# 17_LPDDR4_LPDDR4x_1.net
KiCad netlist of a schematic drawn in Altium Designer
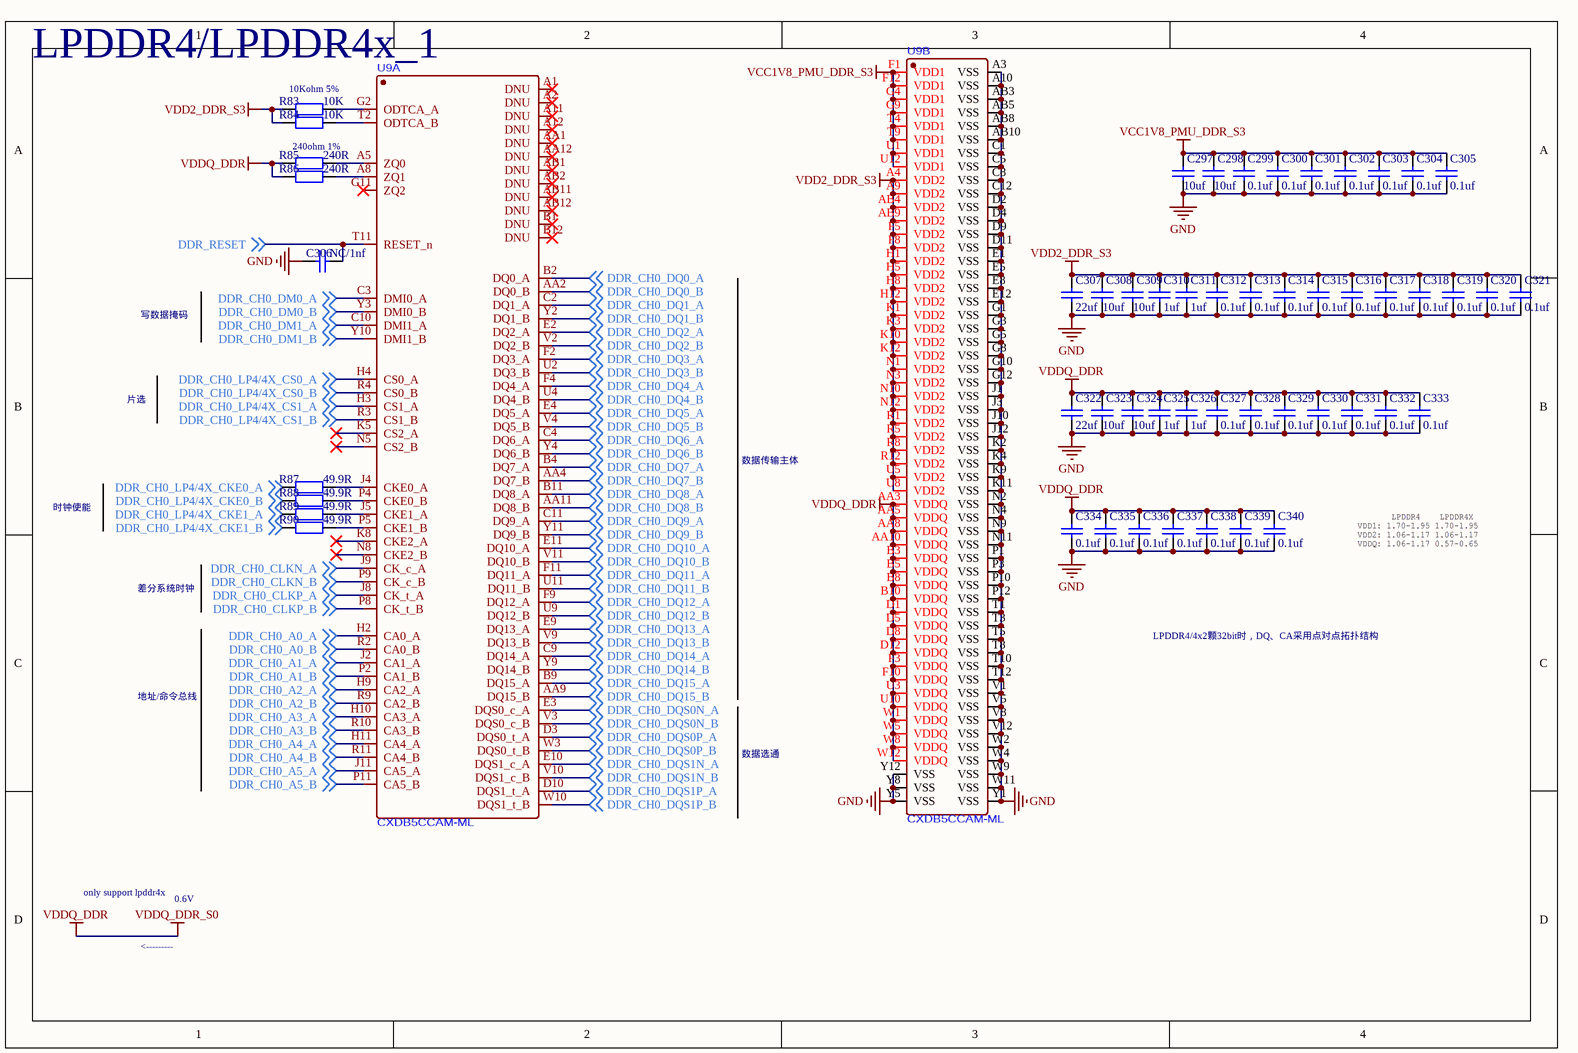
[diagram p0: 17.LPDDR4_LPDDR4x_1.SchDoc]

(export (version "E")
  (design (tool "Eeschema 10.0.6"))
  (components
    (comp (ref "C297")
      (value "10uf")
      (footprint "0.PCB1:C0402_L")
      (description "贴片电容/MLCC电容")
      (libsource (lib "RK3588") (part "C"))
    )
    (comp (ref "C298")
      (value "10uf")
      (footprint "0.PCB1:C0402_L")
      (description "贴片电容/MLCC电容")
      (libsource (lib "RK3588") (part "C"))
    )
    (comp (ref "C299")
      (value "0.1uf")
      (footprint "0.PCB1:C0201_L")
      (description "贴片电容/MLCC电容")
      (libsource (lib "RK3588") (part "C"))
    )
    (comp (ref "C300")
      (value "0.1uf")
      (footprint "0.PCB1:C0201_L")
      (description "贴片电容/MLCC电容")
      (libsource (lib "RK3588") (part "C"))
    )
    (comp (ref "C301")
      (value "0.1uf")
      (footprint "0.PCB1:C0201_L")
      (description "贴片电容/MLCC电容")
      (libsource (lib "RK3588") (part "C"))
    )
    (comp (ref "C302")
      (value "0.1uf")
      (footprint "0.PCB1:C0201_L")
      (description "贴片电容/MLCC电容")
      (libsource (lib "RK3588") (part "C"))
    )
    (comp (ref "C303")
      (value "0.1uf")
      (footprint "0.PCB1:C0201_L")
      (description "贴片电容/MLCC电容")
      (libsource (lib "RK3588") (part "C"))
    )
    (comp (ref "C304")
      (value "0.1uf")
      (footprint "0.PCB1:C0201_L")
      (description "贴片电容/MLCC电容")
      (libsource (lib "RK3588") (part "C"))
    )
    (comp (ref "C305")
      (value "0.1uf")
      (footprint "0.PCB1:C0201_L")
      (description "贴片电容/MLCC电容")
      (libsource (lib "RK3588") (part "C"))
    )
    (comp (ref "C306")
      (value "NC/1nf")
      (footprint "0.PCB1:C0201_L")
      (description "贴片电容/MLCC电容")
      (libsource (lib "RK3588") (part "C"))
    )
    (comp (ref "C307")
      (value "22uf")
      (footprint "0.PCB1:C0603_L")
      (description "贴片电容/MLCC电容")
      (libsource (lib "RK3588") (part "C"))
    )
    (comp (ref "C308")
      (value "10uf")
      (footprint "0.PCB1:C0402_L")
      (description "贴片电容/MLCC电容")
      (libsource (lib "RK3588") (part "C"))
    )
    (comp (ref "C309")
      (value "10uf")
      (footprint "0.PCB1:C0402_L")
      (description "贴片电容/MLCC电容")
      (libsource (lib "RK3588") (part "C"))
    )
    (comp (ref "C310")
      (value "1uf")
      (footprint "0.PCB1:C0201_L")
      (description "贴片电容/MLCC电容")
      (libsource (lib "RK3588") (part "C"))
    )
    (comp (ref "C311")
      (value "1uf")
      (footprint "0.PCB1:C0201_L")
      (description "贴片电容/MLCC电容")
      (libsource (lib "RK3588") (part "C"))
    )
    (comp (ref "C312")
      (value "0.1uf")
      (footprint "0.PCB1:C0201_L")
      (description "贴片电容/MLCC电容")
      (libsource (lib "RK3588") (part "C"))
    )
    (comp (ref "C313")
      (value "0.1uf")
      (footprint "0.PCB1:C0201_L")
      (description "贴片电容/MLCC电容")
      (libsource (lib "RK3588") (part "C"))
    )
    (comp (ref "C314")
      (value "0.1uf")
      (footprint "0.PCB1:C0201_L")
      (description "贴片电容/MLCC电容")
      (libsource (lib "RK3588") (part "C"))
    )
    (comp (ref "C315")
      (value "0.1uf")
      (footprint "0.PCB1:C0201_L")
      (description "贴片电容/MLCC电容")
      (libsource (lib "RK3588") (part "C"))
    )
    (comp (ref "C316")
      (value "0.1uf")
      (footprint "0.PCB1:C0201_L")
      (description "贴片电容/MLCC电容")
      (libsource (lib "RK3588") (part "C"))
    )
    (comp (ref "C317")
      (value "0.1uf")
      (footprint "0.PCB1:C0201_L")
      (description "贴片电容/MLCC电容")
      (libsource (lib "RK3588") (part "C"))
    )
    (comp (ref "C318")
      (value "0.1uf")
      (footprint "0.PCB1:C0201_L")
      (description "贴片电容/MLCC电容")
      (libsource (lib "RK3588") (part "C"))
    )
    (comp (ref "C319")
      (value "0.1uf")
      (footprint "0.PCB1:C0201_L")
      (description "贴片电容/MLCC电容")
      (libsource (lib "RK3588") (part "C"))
    )
    (comp (ref "C320")
      (value "0.1uf")
      (footprint "0.PCB1:C0201_L")
      (description "贴片电容/MLCC电容")
      (libsource (lib "RK3588") (part "C"))
    )
    (comp (ref "C321")
      (value "0.1uf")
      (footprint "0.PCB1:C0201_L")
      (description "贴片电容/MLCC电容")
      (libsource (lib "RK3588") (part "C"))
    )
    (comp (ref "C322")
      (value "22uf")
      (footprint "0.PCB1:C0603_L")
      (description "贴片电容/MLCC电容")
      (libsource (lib "RK3588") (part "C"))
    )
    (comp (ref "C323")
      (value "10uf")
      (footprint "0.PCB1:C0402_L")
      (description "贴片电容/MLCC电容")
      (libsource (lib "RK3588") (part "C"))
    )
    (comp (ref "C324")
      (value "10uf")
      (footprint "0.PCB1:C0402_L")
      (description "贴片电容/MLCC电容")
      (libsource (lib "RK3588") (part "C"))
    )
    (comp (ref "C325")
      (value "1uf")
      (footprint "0.PCB1:C0201_L")
      (description "贴片电容/MLCC电容")
      (libsource (lib "RK3588") (part "C"))
    )
    (comp (ref "C326")
      (value "1uf")
      (footprint "0.PCB1:C0201_L")
      (description "贴片电容/MLCC电容")
      (libsource (lib "RK3588") (part "C"))
    )
    (comp (ref "C327")
      (value "0.1uf")
      (footprint "0.PCB1:C0201_L")
      (description "贴片电容/MLCC电容")
      (libsource (lib "RK3588") (part "C"))
    )
    (comp (ref "C328")
      (value "0.1uf")
      (footprint "0.PCB1:C0201_L")
      (description "贴片电容/MLCC电容")
      (libsource (lib "RK3588") (part "C"))
    )
    (comp (ref "C329")
      (value "0.1uf")
      (footprint "0.PCB1:C0201_L")
      (description "贴片电容/MLCC电容")
      (libsource (lib "RK3588") (part "C"))
    )
    (comp (ref "C330")
      (value "0.1uf")
      (footprint "0.PCB1:C0201_L")
      (description "贴片电容/MLCC电容")
      (libsource (lib "RK3588") (part "C"))
    )
    (comp (ref "C331")
      (value "0.1uf")
      (footprint "0.PCB1:C0201_L")
      (description "贴片电容/MLCC电容")
      (libsource (lib "RK3588") (part "C"))
    )
    (comp (ref "C332")
      (value "0.1uf")
      (footprint "0.PCB1:C0201_L")
      (description "贴片电容/MLCC电容")
      (libsource (lib "RK3588") (part "C"))
    )
    (comp (ref "C333")
      (value "0.1uf")
      (footprint "0.PCB1:C0201_L")
      (description "贴片电容/MLCC电容")
      (libsource (lib "RK3588") (part "C"))
    )
    (comp (ref "C334")
      (value "0.1uf")
      (footprint "0.PCB1:C0201_L")
      (description "贴片电容/MLCC电容")
      (libsource (lib "RK3588") (part "C"))
    )
    (comp (ref "C335")
      (value "0.1uf")
      (footprint "0.PCB1:C0201_L")
      (description "贴片电容/MLCC电容")
      (libsource (lib "RK3588") (part "C"))
    )
    (comp (ref "C336")
      (value "0.1uf")
      (footprint "0.PCB1:C0201_L")
      (description "贴片电容/MLCC电容")
      (libsource (lib "RK3588") (part "C"))
    )
    (comp (ref "C337")
      (value "0.1uf")
      (footprint "0.PCB1:C0201_L")
      (description "贴片电容/MLCC电容")
      (libsource (lib "RK3588") (part "C"))
    )
    (comp (ref "C338")
      (value "0.1uf")
      (footprint "0.PCB1:C0201_L")
      (description "贴片电容/MLCC电容")
      (libsource (lib "RK3588") (part "C"))
    )
    (comp (ref "C339")
      (value "0.1uf")
      (footprint "0.PCB1:C0201_L")
      (description "贴片电容/MLCC电容")
      (libsource (lib "RK3588") (part "C"))
    )
    (comp (ref "C340")
      (value "0.1uf")
      (footprint "0.PCB1:C0201_L")
      (description "贴片电容/MLCC电容")
      (libsource (lib "RK3588") (part "C"))
    )
    (comp (ref "R83")
      (value "10K")
      (footprint "0.PCB1:R0201_L")
      (description "贴片电阻")
      (libsource (lib "RK3588") (part "R"))
    )
    (comp (ref "R84")
      (value "10K")
      (footprint "0.PCB1:R0201_L")
      (description "贴片电阻")
      (libsource (lib "RK3588") (part "R"))
    )
    (comp (ref "R85")
      (value "240R")
      (footprint "0.PCB1:R0201_L")
      (description "贴片电阻")
      (libsource (lib "RK3588") (part "R"))
    )
    (comp (ref "R86")
      (value "240R")
      (footprint "0.PCB1:R0201_L")
      (description "贴片电阻")
      (libsource (lib "RK3588") (part "R"))
    )
    (comp (ref "R87")
      (value "49.9R")
      (footprint "0.PCB1:R0201_L")
      (description "贴片电阻")
      (libsource (lib "RK3588") (part "R"))
    )
    (comp (ref "R88")
      (value "49.9R")
      (footprint "0.PCB1:R0201_L")
      (description "贴片电阻")
      (libsource (lib "RK3588") (part "R"))
    )
    (comp (ref "R89")
      (value "49.9R")
      (footprint "0.PCB1:R0201_L")
      (description "贴片电阻")
      (libsource (lib "RK3588") (part "R"))
    )
    (comp (ref "R90")
      (value "49.9R")
      (footprint "0.PCB1:R0201_L")
      (description "贴片电阻")
      (libsource (lib "RK3588") (part "R"))
    )
    (comp (ref "U9")
      (value "CXDB5CCAM-ML")
      (footprint "0.PCB1:FBGA-200_L15.0-W10.0-BL_K4F6E3S4HM")
      (libsource (lib "RK3588") (part "CXDB5CCAM-ML"))
    )
  )
  (nets
    (net (code "1") (name "DDR_CH0_A0_A") (class "Default")
      (node (ref "U9") (pin "H2") (pinfunction "CA0_A_H2") (pintype "passive"))
    )
    (net (code "2") (name "DDR_CH0_A0_B") (class "Default")
      (node (ref "U9") (pin "R2") (pinfunction "CA0_B_R2") (pintype "passive"))
    )
    (net (code "3") (name "DDR_CH0_A1_A") (class "Default")
      (node (ref "U9") (pin "J2") (pinfunction "CA1_A_J2") (pintype "passive"))
    )
    (net (code "4") (name "DDR_CH0_A1_B") (class "Default")
      (node (ref "U9") (pin "P2") (pinfunction "CA1_B_P2") (pintype "passive"))
    )
    (net (code "5") (name "DDR_CH0_A2_A") (class "Default")
      (node (ref "U9") (pin "H9") (pinfunction "CA2_A_H9") (pintype "passive"))
    )
    (net (code "6") (name "DDR_CH0_A2_B") (class "Default")
      (node (ref "U9") (pin "R9") (pinfunction "CA2_B_R9") (pintype "passive"))
    )
    (net (code "7") (name "DDR_CH0_A3_A") (class "Default")
      (node (ref "U9") (pin "H10") (pinfunction "CA3_A_H10") (pintype "passive"))
    )
    (net (code "8") (name "DDR_CH0_A3_B") (class "Default")
      (node (ref "U9") (pin "R10") (pinfunction "CA3_B_R10") (pintype "passive"))
    )
    (net (code "9") (name "DDR_CH0_A4_A") (class "Default")
      (node (ref "U9") (pin "H11") (pinfunction "CA4_A_H11") (pintype "passive"))
    )
    (net (code "10") (name "DDR_CH0_A4_B") (class "Default")
      (node (ref "U9") (pin "R11") (pinfunction "CA4_B_R11") (pintype "passive"))
    )
    (net (code "11") (name "DDR_CH0_A5_A") (class "Default")
      (node (ref "U9") (pin "J11") (pinfunction "CA5_A_J11") (pintype "passive"))
    )
    (net (code "12") (name "DDR_CH0_A5_B") (class "Default")
      (node (ref "U9") (pin "P11") (pinfunction "CA5_B_P11") (pintype "passive"))
    )
    (net (code "13") (name "DDR_CH0_CLKN_A") (class "Default")
      (node (ref "U9") (pin "J9") (pinfunction "CK_c_A_J9") (pintype "passive"))
    )
    (net (code "14") (name "DDR_CH0_CLKN_B") (class "Default")
      (node (ref "U9") (pin "P9") (pinfunction "CK_c_B_P9") (pintype "passive"))
    )
    (net (code "15") (name "DDR_CH0_CLKP_A") (class "Default")
      (node (ref "U9") (pin "J8") (pinfunction "CK_t_A_J8") (pintype "passive"))
    )
    (net (code "16") (name "DDR_CH0_CLKP_B") (class "Default")
      (node (ref "U9") (pin "P8") (pinfunction "CK_t_B_P8") (pintype "passive"))
    )
    (net (code "17") (name "DDR_CH0_DM0_A") (class "Default")
      (node (ref "U9") (pin "C3") (pinfunction "DMI0_A_C3") (pintype "passive"))
    )
    (net (code "18") (name "DDR_CH0_DM0_B") (class "Default")
      (node (ref "U9") (pin "Y3") (pinfunction "DMI0_B_Y3") (pintype "passive"))
    )
    (net (code "19") (name "DDR_CH0_DM1_A") (class "Default")
      (node (ref "U9") (pin "C10") (pinfunction "DMI1_A_C10") (pintype "passive"))
    )
    (net (code "20") (name "DDR_CH0_DM1_B") (class "Default")
      (node (ref "U9") (pin "Y10") (pinfunction "DMI1_B_Y10") (pintype "passive"))
    )
    (net (code "21") (name "DDR_CH0_DQ0_A") (class "Default")
      (node (ref "U9") (pin "B2") (pinfunction "DQ0_A_B2") (pintype "passive"))
    )
    (net (code "22") (name "DDR_CH0_DQ0_B") (class "Default")
      (node (ref "U9") (pin "AA2") (pinfunction "DQ0_B_AA2") (pintype "passive"))
    )
    (net (code "23") (name "DDR_CH0_DQ1_A") (class "Default")
      (node (ref "U9") (pin "C2") (pinfunction "DQ1_A_C2") (pintype "passive"))
    )
    (net (code "24") (name "DDR_CH0_DQ1_B") (class "Default")
      (node (ref "U9") (pin "Y2") (pinfunction "DQ1_B_Y2") (pintype "passive"))
    )
    (net (code "25") (name "DDR_CH0_DQ2_A") (class "Default")
      (node (ref "U9") (pin "E2") (pinfunction "DQ2_A_E2") (pintype "passive"))
    )
    (net (code "26") (name "DDR_CH0_DQ2_B") (class "Default")
      (node (ref "U9") (pin "V2") (pinfunction "DQ2_B_V2") (pintype "passive"))
    )
    (net (code "27") (name "DDR_CH0_DQ3_A") (class "Default")
      (node (ref "U9") (pin "F2") (pinfunction "DQ3_A_F2") (pintype "passive"))
    )
    (net (code "28") (name "DDR_CH0_DQ3_B") (class "Default")
      (node (ref "U9") (pin "U2") (pinfunction "DQ3_B_U2") (pintype "passive"))
    )
    (net (code "29") (name "DDR_CH0_DQ4_A") (class "Default")
      (node (ref "U9") (pin "F4") (pinfunction "DQ4_A_F4") (pintype "passive"))
    )
    (net (code "30") (name "DDR_CH0_DQ4_B") (class "Default")
      (node (ref "U9") (pin "U4") (pinfunction "DQ4_B_U4") (pintype "passive"))
    )
    (net (code "31") (name "DDR_CH0_DQ5_A") (class "Default")
      (node (ref "U9") (pin "E4") (pinfunction "DQ5_A_E4") (pintype "passive"))
    )
    (net (code "32") (name "DDR_CH0_DQ5_B") (class "Default")
      (node (ref "U9") (pin "V4") (pinfunction "DQ5_B_V4") (pintype "passive"))
    )
    (net (code "33") (name "DDR_CH0_DQ6_A") (class "Default")
      (node (ref "U9") (pin "C4") (pinfunction "DQ6_A_C4") (pintype "passive"))
    )
    (net (code "34") (name "DDR_CH0_DQ6_B") (class "Default")
      (node (ref "U9") (pin "Y4") (pinfunction "DQ6_B_Y4") (pintype "passive"))
    )
    (net (code "35") (name "DDR_CH0_DQ7_A") (class "Default")
      (node (ref "U9") (pin "B4") (pinfunction "DQ7_A_B4") (pintype "passive"))
    )
    (net (code "36") (name "DDR_CH0_DQ7_B") (class "Default")
      (node (ref "U9") (pin "AA4") (pinfunction "DQ7_B_AA4") (pintype "passive"))
    )
    (net (code "37") (name "DDR_CH0_DQ8_A") (class "Default")
      (node (ref "U9") (pin "B11") (pinfunction "DQ8_A_B11") (pintype "passive"))
    )
    (net (code "38") (name "DDR_CH0_DQ8_B") (class "Default")
      (node (ref "U9") (pin "AA11") (pinfunction "DQ8_B_AA11") (pintype "passive"))
    )
    (net (code "39") (name "DDR_CH0_DQ9_A") (class "Default")
      (node (ref "U9") (pin "C11") (pinfunction "DQ9_A_C11") (pintype "passive"))
    )
    (net (code "40") (name "DDR_CH0_DQ9_B") (class "Default")
      (node (ref "U9") (pin "Y11") (pinfunction "DQ9_B_Y11") (pintype "passive"))
    )
    (net (code "41") (name "DDR_CH0_DQ10_A") (class "Default")
      (node (ref "U9") (pin "E11") (pinfunction "DQ10_A_E11") (pintype "passive"))
    )
    (net (code "42") (name "DDR_CH0_DQ10_B") (class "Default")
      (node (ref "U9") (pin "V11") (pinfunction "DQ10_B_V11") (pintype "passive"))
    )
    (net (code "43") (name "DDR_CH0_DQ11_A") (class "Default")
      (node (ref "U9") (pin "F11") (pinfunction "DQ11_A_F11") (pintype "passive"))
    )
    (net (code "44") (name "DDR_CH0_DQ11_B") (class "Default")
      (node (ref "U9") (pin "U11") (pinfunction "DQ11_B_U11") (pintype "passive"))
    )
    (net (code "45") (name "DDR_CH0_DQ12_A") (class "Default")
      (node (ref "U9") (pin "F9") (pinfunction "DQ12_A_F9") (pintype "passive"))
    )
    (net (code "46") (name "DDR_CH0_DQ12_B") (class "Default")
      (node (ref "U9") (pin "U9") (pinfunction "DQ12_B_U9") (pintype "passive"))
    )
    (net (code "47") (name "DDR_CH0_DQ13_A") (class "Default")
      (node (ref "U9") (pin "E9") (pinfunction "DQ13_A_E9") (pintype "passive"))
    )
    (net (code "48") (name "DDR_CH0_DQ13_B") (class "Default")
      (node (ref "U9") (pin "V9") (pinfunction "DQ13_B_V9") (pintype "passive"))
    )
    (net (code "49") (name "DDR_CH0_DQ14_A") (class "Default")
      (node (ref "U9") (pin "C9") (pinfunction "DQ14_A_C9") (pintype "passive"))
    )
    (net (code "50") (name "DDR_CH0_DQ14_B") (class "Default")
      (node (ref "U9") (pin "Y9") (pinfunction "DQ14_B_Y9") (pintype "passive"))
    )
    (net (code "51") (name "DDR_CH0_DQ15_A") (class "Default")
      (node (ref "U9") (pin "B9") (pinfunction "DQ15_A_B9") (pintype "passive"))
    )
    (net (code "52") (name "DDR_CH0_DQ15_B") (class "Default")
      (node (ref "U9") (pin "AA9") (pinfunction "DQ15_B_AA9") (pintype "passive"))
    )
    (net (code "53") (name "DDR_CH0_DQS0N_A") (class "Default")
      (node (ref "U9") (pin "E3") (pinfunction "DQS0_c_A_E3") (pintype "passive"))
    )
    (net (code "54") (name "DDR_CH0_DQS0N_B") (class "Default")
      (node (ref "U9") (pin "V3") (pinfunction "DQS0_c_B_V3") (pintype "passive"))
    )
    (net (code "55") (name "DDR_CH0_DQS0P_A") (class "Default")
      (node (ref "U9") (pin "D3") (pinfunction "DQS0_t_A_D3") (pintype "passive"))
    )
    (net (code "56") (name "DDR_CH0_DQS0P_B") (class "Default")
      (node (ref "U9") (pin "W3") (pinfunction "DQS0_t_B_W3") (pintype "passive"))
    )
    (net (code "57") (name "DDR_CH0_DQS1N_A") (class "Default")
      (node (ref "U9") (pin "E10") (pinfunction "DQS1_c_A_E10") (pintype "passive"))
    )
    (net (code "58") (name "DDR_CH0_DQS1N_B") (class "Default")
      (node (ref "U9") (pin "V10") (pinfunction "DQS1_c_B_V10") (pintype "passive"))
    )
    (net (code "59") (name "DDR_CH0_DQS1P_A") (class "Default")
      (node (ref "U9") (pin "D10") (pinfunction "DQS1_t_A_D10") (pintype "passive"))
    )
    (net (code "60") (name "DDR_CH0_DQS1P_B") (class "Default")
      (node (ref "U9") (pin "W10") (pinfunction "DQS1_t_B_W10") (pintype "passive"))
    )
    (net (code "61") (name "DDR_CH0_LP4{slash}4X_CKE0_A") (class "Default")
      (node (ref "R87") (pin "1") (pinfunction "1_1") (pintype "passive"))
    )
    (net (code "62") (name "DDR_CH0_LP4{slash}4X_CKE0_B") (class "Default")
      (node (ref "R88") (pin "1") (pinfunction "1_1") (pintype "passive"))
    )
    (net (code "63") (name "DDR_CH0_LP4{slash}4X_CKE1_A") (class "Default")
      (node (ref "R89") (pin "1") (pinfunction "1_1") (pintype "passive"))
    )
    (net (code "64") (name "DDR_CH0_LP4{slash}4X_CKE1_B") (class "Default")
      (node (ref "R90") (pin "1") (pinfunction "1_1") (pintype "passive"))
    )
    (net (code "65") (name "DDR_CH0_LP4{slash}4X_CS0_A") (class "Default")
      (node (ref "U9") (pin "H4") (pinfunction "CS0_A_H4") (pintype "passive"))
    )
    (net (code "66") (name "DDR_CH0_LP4{slash}4X_CS0_B") (class "Default")
      (node (ref "U9") (pin "R4") (pinfunction "CS0_B_R4") (pintype "passive"))
    )
    (net (code "67") (name "DDR_CH0_LP4{slash}4X_CS1_A") (class "Default")
      (node (ref "U9") (pin "H3") (pinfunction "CS1_A_H3") (pintype "passive"))
    )
    (net (code "68") (name "DDR_CH0_LP4{slash}4X_CS1_B") (class "Default")
      (node (ref "U9") (pin "R3") (pinfunction "CS1_B_R3") (pintype "passive"))
    )
    (net (code "69") (name "DDR_RESET") (class "Default")
      (node (ref "C306") (pin "2") (pinfunction "2_2") (pintype "passive"))
      (node (ref "U9") (pin "T11") (pinfunction "RESET_n_T11") (pintype "passive"))
    )
    (net (code "70") (name "GND") (class "Default")
      (node (ref "C297") (pin "1") (pinfunction "1_1") (pintype "passive"))
      (node (ref "C298") (pin "1") (pinfunction "1_1") (pintype "passive"))
      (node (ref "C299") (pin "1") (pinfunction "1_1") (pintype "passive"))
      (node (ref "C300") (pin "1") (pinfunction "1_1") (pintype "passive"))
      (node (ref "C301") (pin "1") (pinfunction "1_1") (pintype "passive"))
      (node (ref "C302") (pin "1") (pinfunction "1_1") (pintype "passive"))
      (node (ref "C303") (pin "1") (pinfunction "1_1") (pintype "passive"))
      (node (ref "C304") (pin "1") (pinfunction "1_1") (pintype "passive"))
      (node (ref "C305") (pin "1") (pinfunction "1_1") (pintype "passive"))
      (node (ref "C306") (pin "1") (pinfunction "1_1") (pintype "passive"))
      (node (ref "C307") (pin "1") (pinfunction "1_1") (pintype "passive"))
      (node (ref "C308") (pin "1") (pinfunction "1_1") (pintype "passive"))
      (node (ref "C309") (pin "1") (pinfunction "1_1") (pintype "passive"))
      (node (ref "C310") (pin "1") (pinfunction "1_1") (pintype "passive"))
      (node (ref "C311") (pin "1") (pinfunction "1_1") (pintype "passive"))
      (node (ref "C312") (pin "1") (pinfunction "1_1") (pintype "passive"))
      (node (ref "C313") (pin "1") (pinfunction "1_1") (pintype "passive"))
      (node (ref "C314") (pin "1") (pinfunction "1_1") (pintype "passive"))
      (node (ref "C315") (pin "1") (pinfunction "1_1") (pintype "passive"))
      (node (ref "C316") (pin "1") (pinfunction "1_1") (pintype "passive"))
      (node (ref "C317") (pin "1") (pinfunction "1_1") (pintype "passive"))
      (node (ref "C318") (pin "1") (pinfunction "1_1") (pintype "passive"))
      (node (ref "C319") (pin "1") (pinfunction "1_1") (pintype "passive"))
      (node (ref "C320") (pin "1") (pinfunction "1_1") (pintype "passive"))
      (node (ref "C321") (pin "1") (pinfunction "1_1") (pintype "passive"))
      (node (ref "C322") (pin "1") (pinfunction "1_1") (pintype "passive"))
      (node (ref "C323") (pin "1") (pinfunction "1_1") (pintype "passive"))
      (node (ref "C324") (pin "1") (pinfunction "1_1") (pintype "passive"))
      (node (ref "C325") (pin "1") (pinfunction "1_1") (pintype "passive"))
      (node (ref "C326") (pin "1") (pinfunction "1_1") (pintype "passive"))
      (node (ref "C327") (pin "1") (pinfunction "1_1") (pintype "passive"))
      (node (ref "C328") (pin "1") (pinfunction "1_1") (pintype "passive"))
      (node (ref "C329") (pin "1") (pinfunction "1_1") (pintype "passive"))
      (node (ref "C330") (pin "1") (pinfunction "1_1") (pintype "passive"))
      (node (ref "C331") (pin "1") (pinfunction "1_1") (pintype "passive"))
      (node (ref "C332") (pin "1") (pinfunction "1_1") (pintype "passive"))
      (node (ref "C333") (pin "1") (pinfunction "1_1") (pintype "passive"))
      (node (ref "C334") (pin "1") (pinfunction "1_1") (pintype "passive"))
      (node (ref "C335") (pin "1") (pinfunction "1_1") (pintype "passive"))
      (node (ref "C336") (pin "1") (pinfunction "1_1") (pintype "passive"))
      (node (ref "C337") (pin "1") (pinfunction "1_1") (pintype "passive"))
      (node (ref "C338") (pin "1") (pinfunction "1_1") (pintype "passive"))
      (node (ref "C339") (pin "1") (pinfunction "1_1") (pintype "passive"))
      (node (ref "C340") (pin "1") (pinfunction "1_1") (pintype "passive"))
      (node (ref "U9") (pin "A10") (pinfunction "VSS_A10") (pintype "passive"))
      (node (ref "U9") (pin "A3") (pinfunction "VSS_A3") (pintype "passive"))
      (node (ref "U9") (pin "AB10") (pinfunction "VSS_AB10") (pintype "passive"))
      (node (ref "U9") (pin "AB3") (pinfunction "VSS_AB3") (pintype "passive"))
      (node (ref "U9") (pin "AB5") (pinfunction "VSS_AB5") (pintype "passive"))
      (node (ref "U9") (pin "AB8") (pinfunction "VSS_AB8") (pintype "passive"))
      (node (ref "U9") (pin "C1") (pinfunction "VSS_C1") (pintype "passive"))
      (node (ref "U9") (pin "C12") (pinfunction "VSS_C12") (pintype "passive"))
      (node (ref "U9") (pin "C5") (pinfunction "VSS_C5") (pintype "passive"))
      (node (ref "U9") (pin "C8") (pinfunction "VSS_C8") (pintype "passive"))
      (node (ref "U9") (pin "D11") (pinfunction "VSS_D11") (pintype "passive"))
      (node (ref "U9") (pin "D2") (pinfunction "VSS_D2") (pintype "passive"))
      (node (ref "U9") (pin "D4") (pinfunction "VSS_D4") (pintype "passive"))
      (node (ref "U9") (pin "D9") (pinfunction "VSS_D9") (pintype "passive"))
      (node (ref "U9") (pin "E1") (pinfunction "VSS_E1") (pintype "passive"))
      (node (ref "U9") (pin "E12") (pinfunction "VSS_E12") (pintype "passive"))
      (node (ref "U9") (pin "E5") (pinfunction "VSS_E5") (pintype "passive"))
      (node (ref "U9") (pin "E8") (pinfunction "VSS_E8") (pintype "passive"))
      (node (ref "U9") (pin "G1") (pinfunction "VSS_G1") (pintype "passive"))
      (node (ref "U9") (pin "G10") (pinfunction "VSS_G10") (pintype "passive"))
      (node (ref "U9") (pin "G12") (pinfunction "VSS_G12") (pintype "passive"))
      (node (ref "U9") (pin "G3") (pinfunction "VSS_G3") (pintype "passive"))
      (node (ref "U9") (pin "G5") (pinfunction "VSS_G5") (pintype "passive"))
      (node (ref "U9") (pin "G8") (pinfunction "VSS_G8") (pintype "passive"))
      (node (ref "U9") (pin "J1") (pinfunction "VSS_J1") (pintype "passive"))
      (node (ref "U9") (pin "J10") (pinfunction "VSS_J10") (pintype "passive"))
      (node (ref "U9") (pin "J12") (pinfunction "VSS_J12") (pintype "passive"))
      (node (ref "U9") (pin "J3") (pinfunction "VSS_J3") (pintype "passive"))
      (node (ref "U9") (pin "K11") (pinfunction "VSS_K11") (pintype "passive"))
      (node (ref "U9") (pin "K2") (pinfunction "VSS_K2") (pintype "passive"))
      (node (ref "U9") (pin "K4") (pinfunction "VSS_K4") (pintype "passive"))
      (node (ref "U9") (pin "K9") (pinfunction "VSS_K9") (pintype "passive"))
      (node (ref "U9") (pin "N11") (pinfunction "VSS_N11") (pintype "passive"))
      (node (ref "U9") (pin "N2") (pinfunction "VSS_N2") (pintype "passive"))
      (node (ref "U9") (pin "N4") (pinfunction "VSS_N4") (pintype "passive"))
      (node (ref "U9") (pin "N9") (pinfunction "VSS_N9") (pintype "passive"))
      (node (ref "U9") (pin "P1") (pinfunction "VSS_P1") (pintype "passive"))
      (node (ref "U9") (pin "P10") (pinfunction "VSS_P10") (pintype "passive"))
      (node (ref "U9") (pin "P12") (pinfunction "VSS_P12") (pintype "passive"))
      (node (ref "U9") (pin "P3") (pinfunction "VSS_P3") (pintype "passive"))
      (node (ref "U9") (pin "T1") (pinfunction "VSS_T1") (pintype "passive"))
      (node (ref "U9") (pin "T10") (pinfunction "VSS_T10") (pintype "passive"))
      (node (ref "U9") (pin "T12") (pinfunction "VSS_T12") (pintype "passive"))
      (node (ref "U9") (pin "T3") (pinfunction "VSS_T3") (pintype "passive"))
      (node (ref "U9") (pin "T5") (pinfunction "VSS_T5") (pintype "passive"))
      (node (ref "U9") (pin "T8") (pinfunction "VSS_T8") (pintype "passive"))
      (node (ref "U9") (pin "V1") (pinfunction "VSS_V1") (pintype "passive"))
      (node (ref "U9") (pin "V12") (pinfunction "VSS_V12") (pintype "passive"))
      (node (ref "U9") (pin "V5") (pinfunction "VSS_V5") (pintype "passive"))
      (node (ref "U9") (pin "V8") (pinfunction "VSS_V8") (pintype "passive"))
      (node (ref "U9") (pin "W11") (pinfunction "VSS_W11") (pintype "passive"))
      (node (ref "U9") (pin "W2") (pinfunction "VSS_W2") (pintype "passive"))
      (node (ref "U9") (pin "W4") (pinfunction "VSS_W4") (pintype "passive"))
      (node (ref "U9") (pin "W9") (pinfunction "VSS_W9") (pintype "passive"))
      (node (ref "U9") (pin "Y1") (pinfunction "VSS_Y1") (pintype "passive"))
      (node (ref "U9") (pin "Y12") (pinfunction "VSS_Y12") (pintype "passive"))
      (node (ref "U9") (pin "Y5") (pinfunction "VSS_Y5") (pintype "passive"))
      (node (ref "U9") (pin "Y8") (pinfunction "VSS_Y8") (pintype "passive"))
    )
    (net (code "71") (name "Net-(U9A-CKE0_A)") (class "Default")
      (node (ref "R87") (pin "2") (pinfunction "2_2") (pintype "passive"))
      (node (ref "U9") (pin "J4") (pinfunction "CKE0_A_J4") (pintype "passive"))
    )
    (net (code "72") (name "Net-(U9A-CKE0_B)") (class "Default")
      (node (ref "R88") (pin "2") (pinfunction "2_2") (pintype "passive"))
      (node (ref "U9") (pin "P4") (pinfunction "CKE0_B_P4") (pintype "passive"))
    )
    (net (code "73") (name "Net-(U9A-CKE1_A)") (class "Default")
      (node (ref "R89") (pin "2") (pinfunction "2_2") (pintype "passive"))
      (node (ref "U9") (pin "J5") (pinfunction "CKE1_A_J5") (pintype "passive"))
    )
    (net (code "74") (name "Net-(U9A-CKE1_B)") (class "Default")
      (node (ref "R90") (pin "2") (pinfunction "2_2") (pintype "passive"))
      (node (ref "U9") (pin "P5") (pinfunction "CKE1_B_P5") (pintype "passive"))
    )
    (net (code "75") (name "Net-(U9A-ODTCA_A)") (class "Default")
      (node (ref "R83") (pin "2") (pinfunction "2_2") (pintype "passive"))
      (node (ref "U9") (pin "G2") (pinfunction "ODTCA_A_G2") (pintype "passive"))
    )
    (net (code "76") (name "Net-(U9A-ODTCA_B)") (class "Default")
      (node (ref "R84") (pin "2") (pinfunction "2_2") (pintype "passive"))
      (node (ref "U9") (pin "T2") (pinfunction "ODTCA_B_T2") (pintype "passive"))
    )
    (net (code "77") (name "Net-(U9A-ZQ0)") (class "Default")
      (node (ref "R85") (pin "2") (pinfunction "2_2") (pintype "passive"))
      (node (ref "U9") (pin "A5") (pinfunction "ZQ0_A5") (pintype "passive"))
    )
    (net (code "78") (name "Net-(U9A-ZQ1)") (class "Default")
      (node (ref "R86") (pin "2") (pinfunction "2_2") (pintype "passive"))
      (node (ref "U9") (pin "A8") (pinfunction "ZQ1_A8") (pintype "passive"))
    )
    (net (code "79") (name "VCC1V8_PMU_DDR_S3") (class "Default")
      (node (ref "C297") (pin "2") (pinfunction "2_2") (pintype "passive"))
      (node (ref "C298") (pin "2") (pinfunction "2_2") (pintype "passive"))
      (node (ref "C299") (pin "2") (pinfunction "2_2") (pintype "passive"))
      (node (ref "C300") (pin "2") (pinfunction "2_2") (pintype "passive"))
      (node (ref "C301") (pin "2") (pinfunction "2_2") (pintype "passive"))
      (node (ref "C302") (pin "2") (pinfunction "2_2") (pintype "passive"))
      (node (ref "C303") (pin "2") (pinfunction "2_2") (pintype "passive"))
      (node (ref "C304") (pin "2") (pinfunction "2_2") (pintype "passive"))
      (node (ref "C305") (pin "2") (pinfunction "2_2") (pintype "passive"))
      (node (ref "U9") (pin "F1") (pinfunction "VDD1_F1") (pintype "passive"))
      (node (ref "U9") (pin "F12") (pinfunction "VDD1_F12") (pintype "passive"))
      (node (ref "U9") (pin "G4") (pinfunction "VDD1_G4") (pintype "passive"))
      (node (ref "U9") (pin "G9") (pinfunction "VDD1_G9") (pintype "passive"))
      (node (ref "U9") (pin "T4") (pinfunction "VDD1_T4") (pintype "passive"))
      (node (ref "U9") (pin "T9") (pinfunction "VDD1_T9") (pintype "passive"))
      (node (ref "U9") (pin "U1") (pinfunction "VDD1_U1") (pintype "passive"))
      (node (ref "U9") (pin "U12") (pinfunction "VDD1_U12") (pintype "passive"))
    )
    (net (code "80") (name "VDD2_DDR_S3") (class "Default")
      (node (ref "C307") (pin "2") (pinfunction "2_2") (pintype "passive"))
      (node (ref "C308") (pin "2") (pinfunction "2_2") (pintype "passive"))
      (node (ref "C309") (pin "2") (pinfunction "2_2") (pintype "passive"))
      (node (ref "C310") (pin "2") (pinfunction "2_2") (pintype "passive"))
      (node (ref "C311") (pin "2") (pinfunction "2_2") (pintype "passive"))
      (node (ref "C312") (pin "2") (pinfunction "2_2") (pintype "passive"))
      (node (ref "C313") (pin "2") (pinfunction "2_2") (pintype "passive"))
      (node (ref "C314") (pin "2") (pinfunction "2_2") (pintype "passive"))
      (node (ref "C315") (pin "2") (pinfunction "2_2") (pintype "passive"))
      (node (ref "C316") (pin "2") (pinfunction "2_2") (pintype "passive"))
      (node (ref "C317") (pin "2") (pinfunction "2_2") (pintype "passive"))
      (node (ref "C318") (pin "2") (pinfunction "2_2") (pintype "passive"))
      (node (ref "C319") (pin "2") (pinfunction "2_2") (pintype "passive"))
      (node (ref "C320") (pin "2") (pinfunction "2_2") (pintype "passive"))
      (node (ref "C321") (pin "2") (pinfunction "2_2") (pintype "passive"))
      (node (ref "R83") (pin "1") (pinfunction "1_1") (pintype "passive"))
      (node (ref "R84") (pin "1") (pinfunction "1_1") (pintype "passive"))
      (node (ref "U9") (pin "A4") (pinfunction "VDD2_A4") (pintype "passive"))
      (node (ref "U9") (pin "A9") (pinfunction "VDD2_A9") (pintype "passive"))
      (node (ref "U9") (pin "AB4") (pinfunction "VDD2_AB4") (pintype "passive"))
      (node (ref "U9") (pin "AB9") (pinfunction "VDD2_AB9") (pintype "passive"))
      (node (ref "U9") (pin "F5") (pinfunction "VDD2_F5") (pintype "passive"))
      (node (ref "U9") (pin "F8") (pinfunction "VDD2_F8") (pintype "passive"))
      (node (ref "U9") (pin "H1") (pinfunction "VDD2_H1") (pintype "passive"))
      (node (ref "U9") (pin "H12") (pinfunction "VDD2_H12") (pintype "passive"))
      (node (ref "U9") (pin "H5") (pinfunction "VDD2_H5") (pintype "passive"))
      (node (ref "U9") (pin "H8") (pinfunction "VDD2_H8") (pintype "passive"))
      (node (ref "U9") (pin "K1") (pinfunction "VDD2_K1") (pintype "passive"))
      (node (ref "U9") (pin "K10") (pinfunction "VDD2_K10") (pintype "passive"))
      (node (ref "U9") (pin "K12") (pinfunction "VDD2_K12") (pintype "passive"))
      (node (ref "U9") (pin "K3") (pinfunction "VDD2_K3") (pintype "passive"))
      (node (ref "U9") (pin "N1") (pinfunction "VDD2_N1") (pintype "passive"))
      (node (ref "U9") (pin "N10") (pinfunction "VDD2_N10") (pintype "passive"))
      (node (ref "U9") (pin "N12") (pinfunction "VDD2_N12") (pintype "passive"))
      (node (ref "U9") (pin "N3") (pinfunction "VDD2_N3") (pintype "passive"))
      (node (ref "U9") (pin "R1") (pinfunction "VDD2_R1") (pintype "passive"))
      (node (ref "U9") (pin "R12") (pinfunction "VDD2_R12") (pintype "passive"))
      (node (ref "U9") (pin "R5") (pinfunction "VDD2_R5") (pintype "passive"))
      (node (ref "U9") (pin "R8") (pinfunction "VDD2_R8") (pintype "passive"))
      (node (ref "U9") (pin "U5") (pinfunction "VDD2_U5") (pintype "passive"))
      (node (ref "U9") (pin "U8") (pinfunction "VDD2_U8") (pintype "passive"))
    )
    (net (code "81") (name "VDDQ_DDR") (class "Default")
      (node (ref "C322") (pin "2") (pinfunction "2_2") (pintype "passive"))
      (node (ref "C323") (pin "2") (pinfunction "2_2") (pintype "passive"))
      (node (ref "C324") (pin "2") (pinfunction "2_2") (pintype "passive"))
      (node (ref "C325") (pin "2") (pinfunction "2_2") (pintype "passive"))
      (node (ref "C326") (pin "2") (pinfunction "2_2") (pintype "passive"))
      (node (ref "C327") (pin "2") (pinfunction "2_2") (pintype "passive"))
      (node (ref "C328") (pin "2") (pinfunction "2_2") (pintype "passive"))
      (node (ref "C329") (pin "2") (pinfunction "2_2") (pintype "passive"))
      (node (ref "C330") (pin "2") (pinfunction "2_2") (pintype "passive"))
      (node (ref "C331") (pin "2") (pinfunction "2_2") (pintype "passive"))
      (node (ref "C332") (pin "2") (pinfunction "2_2") (pintype "passive"))
      (node (ref "C333") (pin "2") (pinfunction "2_2") (pintype "passive"))
      (node (ref "C334") (pin "2") (pinfunction "2_2") (pintype "passive"))
      (node (ref "C335") (pin "2") (pinfunction "2_2") (pintype "passive"))
      (node (ref "C336") (pin "2") (pinfunction "2_2") (pintype "passive"))
      (node (ref "C337") (pin "2") (pinfunction "2_2") (pintype "passive"))
      (node (ref "C338") (pin "2") (pinfunction "2_2") (pintype "passive"))
      (node (ref "C339") (pin "2") (pinfunction "2_2") (pintype "passive"))
      (node (ref "C340") (pin "2") (pinfunction "2_2") (pintype "passive"))
      (node (ref "R85") (pin "1") (pinfunction "1_1") (pintype "passive"))
      (node (ref "R86") (pin "1") (pinfunction "1_1") (pintype "passive"))
      (node (ref "U9") (pin "AA10") (pinfunction "VDDQ_AA10") (pintype "passive"))
      (node (ref "U9") (pin "AA3") (pinfunction "VDDQ_AA3") (pintype "passive"))
      (node (ref "U9") (pin "AA5") (pinfunction "VDDQ_AA5") (pintype "passive"))
      (node (ref "U9") (pin "AA8") (pinfunction "VDDQ_AA8") (pintype "passive"))
      (node (ref "U9") (pin "B10") (pinfunction "VDDQ_B10") (pintype "passive"))
      (node (ref "U9") (pin "B3") (pinfunction "VDDQ_B3") (pintype "passive"))
      (node (ref "U9") (pin "B5") (pinfunction "VDDQ_B5") (pintype "passive"))
      (node (ref "U9") (pin "B8") (pinfunction "VDDQ_B8") (pintype "passive"))
      (node (ref "U9") (pin "D1") (pinfunction "VDDQ_D1") (pintype "passive"))
      (node (ref "U9") (pin "D12") (pinfunction "VDDQ_D12") (pintype "passive"))
      (node (ref "U9") (pin "D5") (pinfunction "VDDQ_D5") (pintype "passive"))
      (node (ref "U9") (pin "D8") (pinfunction "VDDQ_D8") (pintype "passive"))
      (node (ref "U9") (pin "F10") (pinfunction "VDDQ_F10") (pintype "passive"))
      (node (ref "U9") (pin "F3") (pinfunction "VDDQ_F3") (pintype "passive"))
      (node (ref "U9") (pin "U10") (pinfunction "VDDQ_U10") (pintype "passive"))
      (node (ref "U9") (pin "U3") (pinfunction "VDDQ_U3") (pintype "passive"))
      (node (ref "U9") (pin "W1") (pinfunction "VDDQ_W1") (pintype "passive"))
      (node (ref "U9") (pin "W12") (pinfunction "VDDQ_W12") (pintype "passive"))
      (node (ref "U9") (pin "W5") (pinfunction "VDDQ_W5") (pintype "passive"))
      (node (ref "U9") (pin "W8") (pinfunction "VDDQ_W8") (pintype "passive"))
    )
    (net (code "82") (name "unconnected-(U9A-CKE2_A-PadK8)") (class "Default")
      (node (ref "U9") (pin "K8") (pinfunction "CKE2_A_K8") (pintype "passive+no_connect"))
    )
    (net (code "83") (name "unconnected-(U9A-CKE2_B-PadN8)") (class "Default")
      (node (ref "U9") (pin "N8") (pinfunction "CKE2_B_N8") (pintype "passive+no_connect"))
    )
    (net (code "84") (name "unconnected-(U9A-CS2_A-PadK5)") (class "Default")
      (node (ref "U9") (pin "K5") (pinfunction "CS2_A_K5") (pintype "passive+no_connect"))
    )
    (net (code "85") (name "unconnected-(U9A-CS2_B-PadN5)") (class "Default")
      (node (ref "U9") (pin "N5") (pinfunction "CS2_B_N5") (pintype "passive+no_connect"))
    )
    (net (code "86") (name "unconnected-(U9A-DNU-PadA1)") (class "Default")
      (node (ref "U9") (pin "A1") (pinfunction "DNU_A1") (pintype "passive+no_connect"))
    )
    (net (code "87") (name "unconnected-(U9A-DNU-PadA2)") (class "Default")
      (node (ref "U9") (pin "A2") (pinfunction "DNU_A2") (pintype "passive+no_connect"))
    )
    (net (code "88") (name "unconnected-(U9A-DNU-PadA11)") (class "Default")
      (node (ref "U9") (pin "A11") (pinfunction "DNU_A11") (pintype "passive+no_connect"))
    )
    (net (code "89") (name "unconnected-(U9A-DNU-PadA12)") (class "Default")
      (node (ref "U9") (pin "A12") (pinfunction "DNU_A12") (pintype "passive+no_connect"))
    )
    (net (code "90") (name "unconnected-(U9A-DNU-PadAA1)") (class "Default")
      (node (ref "U9") (pin "AA1") (pinfunction "DNU_AA1") (pintype "passive+no_connect"))
    )
    (net (code "91") (name "unconnected-(U9A-DNU-PadAA12)") (class "Default")
      (node (ref "U9") (pin "AA12") (pinfunction "DNU_AA12") (pintype "passive+no_connect"))
    )
    (net (code "92") (name "unconnected-(U9A-DNU-PadAB1)") (class "Default")
      (node (ref "U9") (pin "AB1") (pinfunction "DNU_AB1") (pintype "passive+no_connect"))
    )
    (net (code "93") (name "unconnected-(U9A-DNU-PadAB2)") (class "Default")
      (node (ref "U9") (pin "AB2") (pinfunction "DNU_AB2") (pintype "passive+no_connect"))
    )
    (net (code "94") (name "unconnected-(U9A-DNU-PadAB11)") (class "Default")
      (node (ref "U9") (pin "AB11") (pinfunction "DNU_AB11") (pintype "passive+no_connect"))
    )
    (net (code "95") (name "unconnected-(U9A-DNU-PadAB12)") (class "Default")
      (node (ref "U9") (pin "AB12") (pinfunction "DNU_AB12") (pintype "passive+no_connect"))
    )
    (net (code "96") (name "unconnected-(U9A-DNU-PadB1)") (class "Default")
      (node (ref "U9") (pin "B1") (pinfunction "DNU_B1") (pintype "passive+no_connect"))
    )
    (net (code "97") (name "unconnected-(U9A-DNU-PadB12)") (class "Default")
      (node (ref "U9") (pin "B12") (pinfunction "DNU_B12") (pintype "passive+no_connect"))
    )
    (net (code "98") (name "unconnected-(U9A-ZQ2-PadG11)") (class "Default")
      (node (ref "U9") (pin "G11") (pinfunction "ZQ2_G11") (pintype "passive+no_connect"))
    )
  )
)
